# 3V3_High_Current.net
KiCad netlist of a schematic drawn in Altium Designer
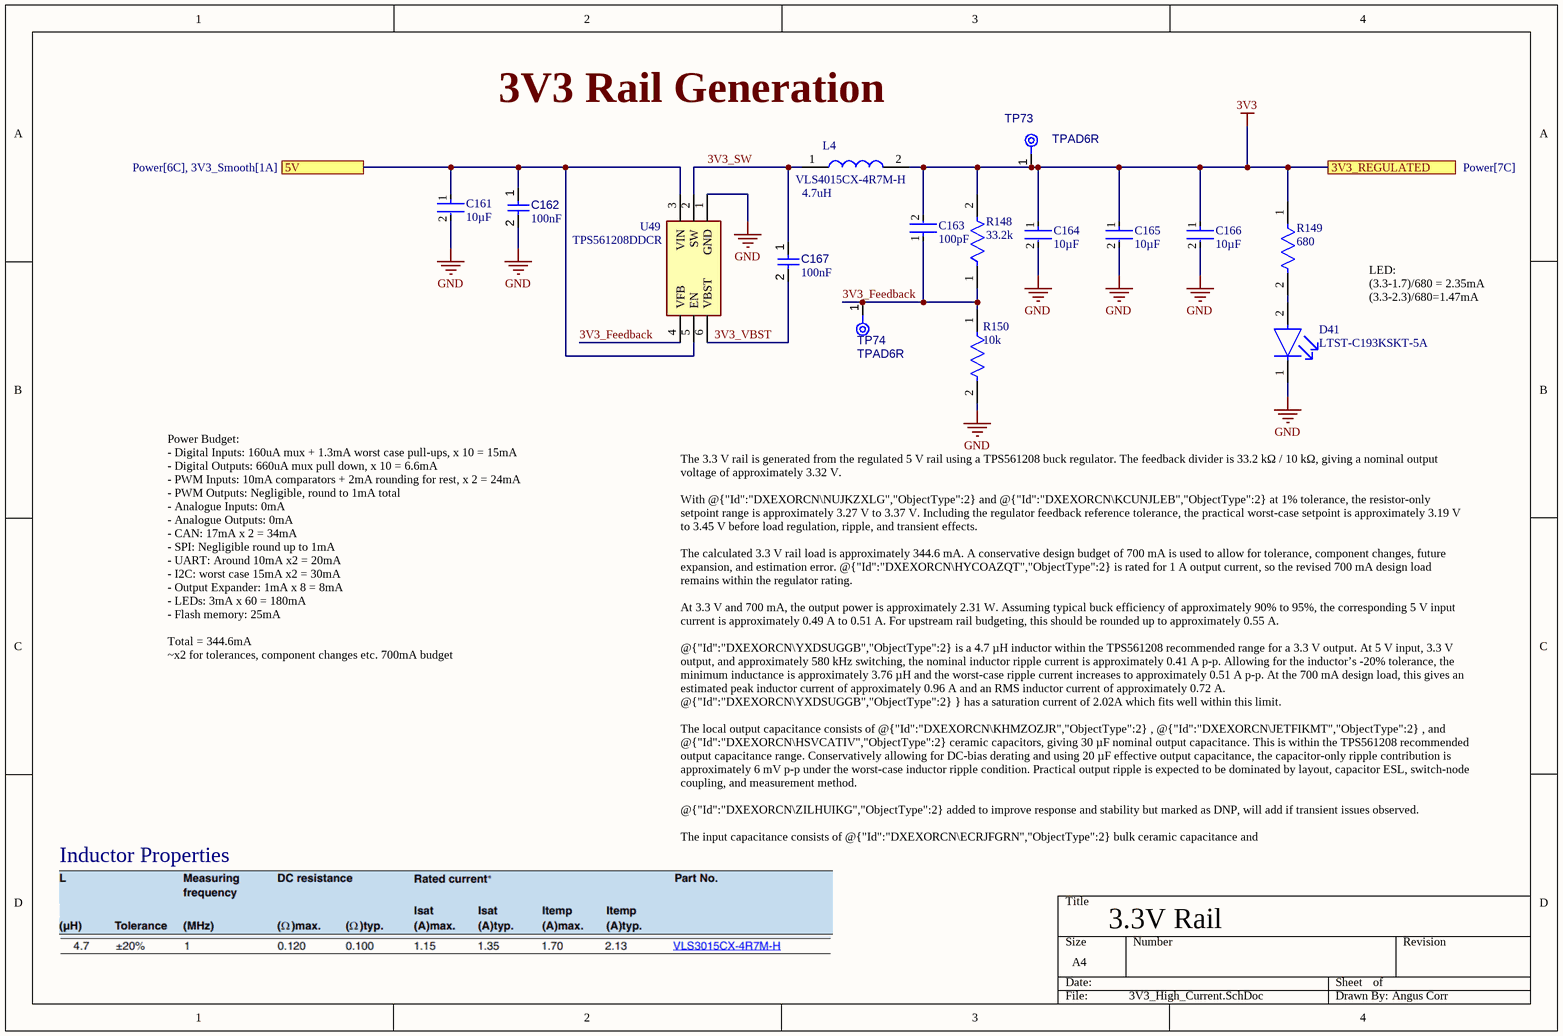
[diagram p0:  3V3_High_Current.SchDoc]

(export (version "E")
  (design (tool "Eeschema 10.0.6"))
  (components
    (comp (ref "C161")
      (value "10µF")
      (footprint "FP-GRM31C-0_2-e0_3_0_8-IPC_C")
      (description "25V 10uF X7R ±10% 1206 Multilayer Ceramic Capacitors MLCC - SMD/SMT ROHS")
      (fields (field (name "TOLERANCE") "10%") (field (name "VOLTAGE") "25V"))
      (libsource (lib "HIL RIG FYP") (part "02cd4be3c70576c341d710602a673aa"))
    )
    (comp (ref "C162")
      (value "100nF")
      (footprint "CAPC1608X90X40NL10T20")
      (description "Chip Capacitor, 100 nF, +/- 10%, 50 V, 0603 (1608 Metric)")
      (fields (field (name "TOLERANCE") "10%") (field (name "Comment") "Capacitor 100 nF +/-10% 50 V 0603"))
      (libsource (lib "HIL RIG FYP") (part "CAP-NP-2"))
    )
    (comp (ref "C163")
      (value "100pF")
      (footprint "FP-C0603C-CF-IPC_B")
      (description "Multilayer Ceramic Capacitors MLCC - SMD/SMT 50V 100pF X8R 0603 1%")
      (fields (field (name "Comment") "C0603C101F5HACTU"))
      (libsource (lib "HIL RIG FYP") (part "b4654b650e69147ec39a6b967a45e02"))
    )
    (comp (ref "C164")
      (value "10µF")
      (footprint "FP-GRM31C-0_2-e0_3_0_8-IPC_C")
      (description "25V 10uF X7R ±10% 1206 Multilayer Ceramic Capacitors MLCC - SMD/SMT ROHS")
      (fields (field (name "TOLERANCE") "10%") (field (name "VOLTAGE") "25V"))
      (libsource (lib "HIL RIG FYP") (part "02cd4be3c70576c341d710602a673aa"))
    )
    (comp (ref "C165")
      (value "10µF")
      (footprint "FP-GRM31C-0_2-e0_3_0_8-IPC_C")
      (description "25V 10uF X7R ±10% 1206 Multilayer Ceramic Capacitors MLCC - SMD/SMT ROHS")
      (fields (field (name "TOLERANCE") "10%") (field (name "VOLTAGE") "25V"))
      (libsource (lib "HIL RIG FYP") (part "02cd4be3c70576c341d710602a673aa"))
    )
    (comp (ref "C166")
      (value "10µF")
      (footprint "FP-GRM31C-0_2-e0_3_0_8-IPC_C")
      (description "25V 10uF X7R ±10% 1206 Multilayer Ceramic Capacitors MLCC - SMD/SMT ROHS")
      (fields (field (name "TOLERANCE") "10%") (field (name "VOLTAGE") "25V"))
      (libsource (lib "HIL RIG FYP") (part "02cd4be3c70576c341d710602a673aa"))
    )
    (comp (ref "C167")
      (value "100nF")
      (footprint "CAPC1608X90X40NL10T20")
      (description "Chip Capacitor, 100 nF, +/- 10%, 50 V, 0603 (1608 Metric)")
      (fields (field (name "TOLERANCE") "10%") (field (name "Comment") "Capacitor 100 nF +/-10% 50 V 0603"))
      (libsource (lib "HIL RIG FYP") (part "CAP-NP-2"))
    )
    (comp (ref "D41")
      (value "LTST-C193KSKT-5A")
      (footprint "FP-LTST-C193KGKT-5A-MFG")
      (description "LED yellow 0603 wavelength 587~594.5nm light intensity 7.1~45mcd Front Mounting")
      (libsource (lib "HIL RIG FYP") (part "8706943c75ba83719d021d2fdc84c58"))
    )
    (comp (ref "L4")
      (value "VLS4015CX-4R7M-H")
      (footprint "VLS4015CX100MH")
      (description "SMD / SMT Inductors (Coils)")
      (fields (field (name "MOUSER PART NUMBER") "810-VLS4015CX-4R7M-H"))
      (libsource (lib "HIL RIG FYP") (part "VLS4015CX-4R7M-H"))
    )
    (comp (ref "R148")
      (value "33.2k")
      (footprint "FP-RT0603-IPC_C")
      (description "100mW Thin Film Resistor 75V ±25ppm/℃ ±0.1% 33.2kΩ 0603 Chip Resistor - Surface Mount ROHS")
      (fields (field (name "TOLERANCE") "0.1%") (field (name "Comment") "RT0603BRD0733K2L"))
      (libsource (lib "HIL RIG FYP") (part "1029c3af85768c4190bb7ad29bc67b5"))
    )
    (comp (ref "R149")
      (value "680")
      (footprint "FP-CRCW0603-e3-IPC_C")
      (description "Fixed Resistor, Metal Glaze/Thick Film, 0.1W, 680ohm, 75V, 5% +/-Tol, Surface Mount, 0603")
      (fields (field (name "TOLERANCE") "5%") (field (name "Comment") "CRCW0603680RJNEA"))
      (libsource (lib "HIL RIG FYP") (part "1029c3af85768c4190bb7ad29bc67b5"))
    )
    (comp (ref "R150")
      (value "10k")
      (footprint "FP-RT0603-IPC_C")
      (description "Res Thin Film 0603 10K Ohm 0.1% 1/10W ¦25ppm/¦C SMD Paper T/R")
      (fields (field (name "TOLERANCE") "0.1%") (field (name "Comment") "RT0603BRD0710KL"))
      (libsource (lib "HIL RIG FYP") (part "1029c3af85768c4190bb7ad29bc67b5"))
    )
    (comp (ref "TP73")
      (value "TPAD6R")
      (footprint "TP06R")
      (description "0.6mm round")
      (libsource (lib "HIL RIG FYP") (part "CMP-001-0001-4"))
    )
    (comp (ref "TP74")
      (value "TPAD6R")
      (footprint "TP06R")
      (description "0.6mm round")
      (libsource (lib "HIL RIG FYP") (part "CMP-001-0001-4"))
    )
    (comp (ref "U49")
      (value "TPS561208DDCR")
      (footprint "SOT95P280X110-6N")
      (description "4.5V to 17V Input")
      (fields (field (name "MOUSER PART NUMBER") "595-TPS561208DDCR"))
      (libsource (lib "HIL RIG FYP") (part "TPS561208DDCR"))
    )
  )
  (nets
    (net (code "1") (name "/3V3_Feedback") (class "Default")
      (node (ref "C163") (pin "1") (pinfunction "1_1") (pintype "passive"))
      (node (ref "R148") (pin "1") (pinfunction "1_1") (pintype "passive"))
      (node (ref "R150") (pin "1") (pinfunction "1_1") (pintype "passive"))
      (node (ref "TP74") (pin "1") (pinfunction "TP_1") (pintype "passive"))
      (node (ref "U49") (pin "4") (pinfunction "VFB_4") (pintype "passive"))
    )
    (net (code "2") (name "/3V3_SW") (class "Default")
      (node (ref "C167") (pin "1") (pinfunction "1_1") (pintype "passive"))
      (node (ref "L4") (pin "1") (pinfunction "1_1") (pintype "passive"))
      (node (ref "U49") (pin "2") (pinfunction "SW_2") (pintype "passive"))
    )
    (net (code "3") (name "/3V3_VBST") (class "Default")
      (node (ref "C167") (pin "2") (pinfunction "2_2") (pintype "passive"))
      (node (ref "U49") (pin "6") (pinfunction "VBST_6") (pintype "passive"))
    )
    (net (code "4") (name "/5V") (class "Default")
      (node (ref "C161") (pin "1") (pinfunction "1_1") (pintype "passive"))
      (node (ref "C162") (pin "1") (pinfunction "1_1") (pintype "passive"))
      (node (ref "U49") (pin "3") (pinfunction "VIN_3") (pintype "passive"))
      (node (ref "U49") (pin "5") (pinfunction "EN_5") (pintype "passive"))
    )
    (net (code "5") (name "3V3") (class "Default")
      (node (ref "C163") (pin "2") (pinfunction "2_2") (pintype "passive"))
      (node (ref "C164") (pin "1") (pinfunction "1_1") (pintype "passive"))
      (node (ref "C165") (pin "1") (pinfunction "1_1") (pintype "passive"))
      (node (ref "C166") (pin "1") (pinfunction "1_1") (pintype "passive"))
      (node (ref "L4") (pin "2") (pinfunction "2_2") (pintype "passive"))
      (node (ref "R148") (pin "2") (pinfunction "2_2") (pintype "passive"))
      (node (ref "R149") (pin "1") (pinfunction "1_1") (pintype "passive"))
      (node (ref "TP73") (pin "1") (pinfunction "TP_1") (pintype "passive"))
    )
    (net (code "6") (name "GND") (class "Default")
      (node (ref "C161") (pin "2") (pinfunction "2_2") (pintype "passive"))
      (node (ref "C162") (pin "2") (pinfunction "2_2") (pintype "passive"))
      (node (ref "C164") (pin "2") (pinfunction "2_2") (pintype "passive"))
      (node (ref "C165") (pin "2") (pinfunction "2_2") (pintype "passive"))
      (node (ref "C166") (pin "2") (pinfunction "2_2") (pintype "passive"))
      (node (ref "D41") (pin "1") (pinfunction "C_1") (pintype "passive"))
      (node (ref "R150") (pin "2") (pinfunction "2_2") (pintype "passive"))
      (node (ref "U49") (pin "1") (pinfunction "GND_1") (pintype "passive"))
    )
    (net (code "7") (name "Net-(D41-A)") (class "Default")
      (node (ref "D41") (pin "2") (pinfunction "A_2") (pintype "passive"))
      (node (ref "R149") (pin "2") (pinfunction "2_2") (pintype "passive"))
    )
  )
)
